# Modulo_Telemetros.net
KiCad netlist of a schematic drawn in Altium Designer
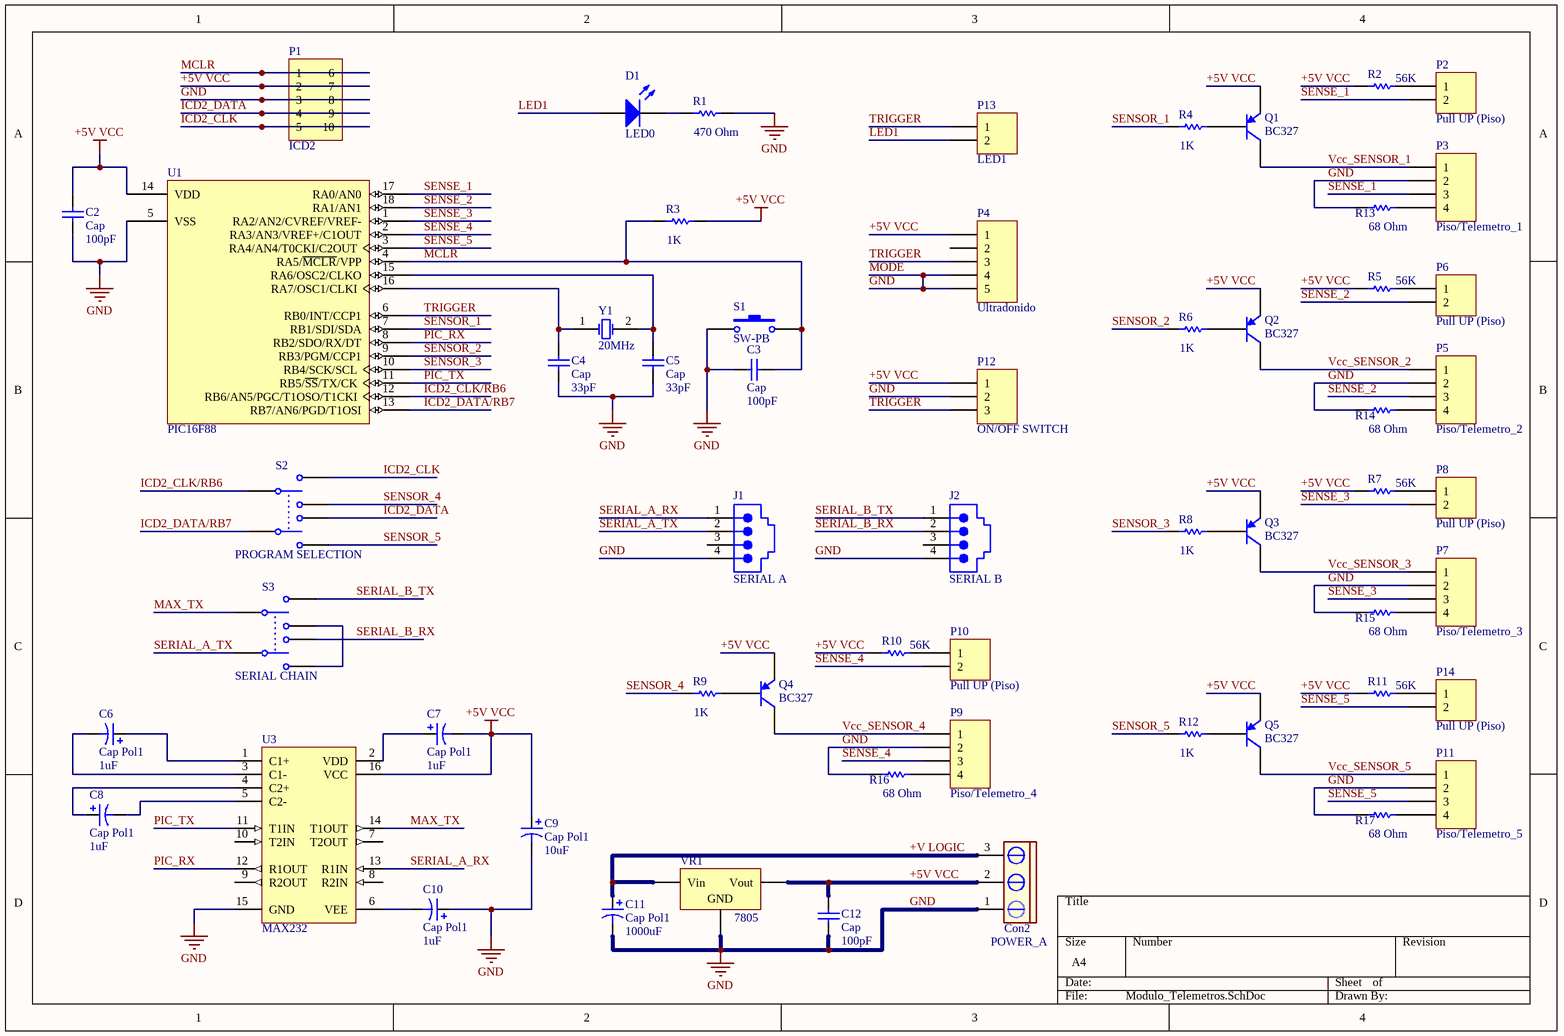
[diagram p0: Modulo_Telemetros.SchDoc]

(export (version "E")
  (design (tool "Eeschema 10.0.6"))
  (components
    (comp (ref "C2")
      (value "Cap")
      (footprint "CAPR2.54-5.1x3.2")
      (description "Capacitor")
      (fields (field (name "ALTIUM_VALUE") "100pF") (field (name "PUBLISHER") "Altium Limited"))
      (libsource (lib "Miscellaneous Devices") (part "Cap"))
    )
    (comp (ref "C3")
      (value "Cap")
      (footprint "CAPR2.54-5.1x3.2")
      (description "Capacitor")
      (fields (field (name "ALTIUM_VALUE") "100pF") (field (name "PUBLISHER") "Altium Limited"))
      (libsource (lib "Miscellaneous Devices") (part "Cap"))
    )
    (comp (ref "C4")
      (value "Cap")
      (footprint "CAPR2.54-5.1x3.2")
      (description "Capacitor")
      (fields (field (name "ALTIUM_VALUE") "33pF") (field (name "PUBLISHER") "Altium Limited"))
      (libsource (lib "Miscellaneous Devices") (part "Cap"))
    )
    (comp (ref "C5")
      (value "Cap")
      (footprint "CAPR2.54-5.1x3.2")
      (description "Capacitor")
      (fields (field (name "ALTIUM_VALUE") "33pF") (field (name "PUBLISHER") "Altium Limited"))
      (libsource (lib "Miscellaneous Devices") (part "Cap"))
    )
    (comp (ref "C6")
      (value "Cap Pol1")
      (footprint "CAPPR2-5x6.8")
      (description "Polarized Capacitor (Radial)")
      (fields (field (name "ALTIUM_VALUE") "1uF") (field (name "PUBLISHER") "Altium Limited"))
      (libsource (lib "Miscellaneous Devices") (part "Cap Pol1"))
    )
    (comp (ref "C7")
      (value "Cap Pol1")
      (footprint "CAPPR2-5x6.8")
      (description "Polarized Capacitor (Radial)")
      (fields (field (name "ALTIUM_VALUE") "1uF") (field (name "PUBLISHER") "Altium Limited"))
      (libsource (lib "Miscellaneous Devices") (part "Cap Pol1"))
    )
    (comp (ref "C8")
      (value "Cap Pol1")
      (footprint "CAPPR2-5x6.8")
      (description "Polarized Capacitor (Radial)")
      (fields (field (name "ALTIUM_VALUE") "1uF") (field (name "PUBLISHER") "Altium Limited"))
      (libsource (lib "Miscellaneous Devices") (part "Cap Pol1"))
    )
    (comp (ref "C9")
      (value "Cap Pol1")
      (footprint "CAPPR2-5x6.8")
      (description "Polarized Capacitor (Radial)")
      (fields (field (name "ALTIUM_VALUE") "10uF") (field (name "PUBLISHER") "Altium Limited"))
      (libsource (lib "Miscellaneous Devices") (part "Cap Pol1"))
    )
    (comp (ref "C10")
      (value "Cap Pol1")
      (footprint "CAPPR2-5x6.8")
      (description "Polarized Capacitor (Radial)")
      (fields (field (name "ALTIUM_VALUE") "1uF") (field (name "PUBLISHER") "Altium Limited"))
      (libsource (lib "Miscellaneous Devices") (part "Cap Pol1"))
    )
    (comp (ref "C11")
      (value "Cap Pol1")
      (footprint "RB5-10.5")
      (description "Polarized Capacitor (Radial)")
      (fields (field (name "ALTIUM_VALUE") "1000uF") (field (name "PUBLISHER") "Altium Limited"))
      (libsource (lib "Miscellaneous Devices") (part "Cap Pol1"))
    )
    (comp (ref "C12")
      (value "Cap")
      (footprint "CAPR2.54-5.1x3.2")
      (description "Capacitor")
      (fields (field (name "ALTIUM_VALUE") "100pF") (field (name "PUBLISHER") "Altium Limited"))
      (libsource (lib "Miscellaneous Devices") (part "Cap"))
    )
    (comp (ref "Con2")
      (value "POWER_A")
      (footprint "My_CN3")
      (description "Connector green screw")
      (libsource (lib "Protel_Library") (part "CON3 pin Green"))
    )
    (comp (ref "D1")
      (value "LED0")
      (footprint "LED-0")
      (description "Typical INFRARED GaAs LED")
      (fields (field (name "PUBLISHER") "Altium Limited"))
      (libsource (lib "Miscellaneous Devices") (part "LED0"))
    )
    (comp (ref "J1")
      (value "SERIAL A")
      (footprint "15-43-6245")
      (description "Right Angle, Standard Profile, RJ45-Keyed, Flange Mount PCB Jack")
      (fields (field (name "PUBLISHER") "Altium Limited"))
      (libsource (lib "Molex Modular Jack Right Angle") (part "15-43-6245"))
    )
    (comp (ref "J2")
      (value "SERIAL B")
      (footprint "15-43-6245")
      (description "Right Angle, Standard Profile, RJ45-Keyed, Flange Mount PCB Jack")
      (fields (field (name "PUBLISHER") "Altium Limited"))
      (libsource (lib "Molex Modular Jack Right Angle") (part "15-43-6245"))
    )
    (comp (ref "P1")
      (value "ICD2")
      (footprint "HEADER10_5x2_B")
      (description "Header, 5-Pin, Dual row")
      (fields (field (name "PUBLISHER") "Altium Limited"))
      (libsource (lib "Miscellaneous Connectors") (part "Header 5X2A"))
    )
    (comp (ref "P2")
      (value "Pull UP (Piso)")
      (footprint "HDR1X2")
      (description "Header, 2-Pin")
      (fields (field (name "PUBLISHER") "Altium Limited"))
      (libsource (lib "Miscellaneous Connectors") (part "Header 2"))
    )
    (comp (ref "P3")
      (value "Piso/Telemetro_1")
      (footprint "HDR1X4")
      (description "Header, 4-Pin")
      (fields (field (name "PUBLISHER") "Altium Limited"))
      (libsource (lib "Miscellaneous Connectors") (part "Header 4"))
    )
    (comp (ref "P4")
      (value "Ultradonido")
      (footprint "HDR1X5")
      (description "Header, 5-Pin")
      (fields (field (name "PUBLISHER") "Altium Limited"))
      (libsource (lib "Miscellaneous Connectors") (part "Header 5"))
    )
    (comp (ref "P5")
      (value "Piso/Telemetro_2")
      (footprint "HDR1X4")
      (description "Header, 4-Pin")
      (fields (field (name "PUBLISHER") "Altium Limited"))
      (libsource (lib "Miscellaneous Connectors") (part "Header 4"))
    )
    (comp (ref "P6")
      (value "Pull UP (Piso)")
      (footprint "HDR1X2")
      (description "Header, 2-Pin")
      (fields (field (name "PUBLISHER") "Altium Limited"))
      (libsource (lib "Miscellaneous Connectors") (part "Header 2"))
    )
    (comp (ref "P7")
      (value "Piso/Telemetro_3")
      (footprint "HDR1X4")
      (description "Header, 4-Pin")
      (fields (field (name "PUBLISHER") "Altium Limited"))
      (libsource (lib "Miscellaneous Connectors") (part "Header 4"))
    )
    (comp (ref "P8")
      (value "Pull UP (Piso)")
      (footprint "HDR1X2")
      (description "Header, 2-Pin")
      (fields (field (name "PUBLISHER") "Altium Limited"))
      (libsource (lib "Miscellaneous Connectors") (part "Header 2"))
    )
    (comp (ref "P9")
      (value "Piso/Telemetro_4")
      (footprint "HDR1X4")
      (description "Header, 4-Pin")
      (fields (field (name "PUBLISHER") "Altium Limited"))
      (libsource (lib "Miscellaneous Connectors") (part "Header 4"))
    )
    (comp (ref "P10")
      (value "Pull UP (Piso)")
      (footprint "HDR1X2")
      (description "Header, 2-Pin")
      (fields (field (name "PUBLISHER") "Altium Limited"))
      (libsource (lib "Miscellaneous Connectors") (part "Header 2"))
    )
    (comp (ref "P11")
      (value "Piso/Telemetro_5")
      (footprint "HDR1X4")
      (description "Header, 4-Pin")
      (fields (field (name "PUBLISHER") "Altium Limited"))
      (libsource (lib "Miscellaneous Connectors") (part "Header 4"))
    )
    (comp (ref "P12")
      (value "ON/OFF SWITCH")
      (footprint "HDR1X3")
      (description "Header, 3-Pin")
      (fields (field (name "PUBLISHER") "Altium Limited"))
      (libsource (lib "Miscellaneous Connectors") (part "Header 3"))
    )
    (comp (ref "P13")
      (value "LED1")
      (footprint "HDR1X2")
      (description "Header, 2-Pin")
      (fields (field (name "PUBLISHER") "Altium Limited"))
      (libsource (lib "Miscellaneous Connectors") (part "Header 2"))
    )
    (comp (ref "P14")
      (value "Pull UP (Piso)")
      (footprint "HDR1X2")
      (description "Header, 2-Pin")
      (fields (field (name "PUBLISHER") "Altium Limited"))
      (libsource (lib "Miscellaneous Connectors") (part "Header 2"))
    )
    (comp (ref "Q1")
      (value "BC327")
      (footprint "TO-92A")
      (description "PNP Switching Transistor")
      (fields (field (name "PUBLISHER") "Altium Limited"))
      (libsource (lib "FSC Discrete BJT") (part "2N5771"))
    )
    (comp (ref "Q2")
      (value "BC327")
      (footprint "TO-92A")
      (description "PNP Switching Transistor")
      (fields (field (name "PUBLISHER") "Altium Limited"))
      (libsource (lib "FSC Discrete BJT") (part "2N5771"))
    )
    (comp (ref "Q3")
      (value "BC327")
      (footprint "TO-92A")
      (description "PNP Switching Transistor")
      (fields (field (name "PUBLISHER") "Altium Limited"))
      (libsource (lib "FSC Discrete BJT") (part "2N5771"))
    )
    (comp (ref "Q4")
      (value "BC327")
      (footprint "TO-92A")
      (description "PNP Switching Transistor")
      (fields (field (name "PUBLISHER") "Altium Limited"))
      (libsource (lib "FSC Discrete BJT") (part "2N5771"))
    )
    (comp (ref "Q5")
      (value "BC327")
      (footprint "TO-92A")
      (description "PNP Switching Transistor")
      (fields (field (name "PUBLISHER") "Altium Limited"))
      (libsource (lib "FSC Discrete BJT") (part "2N5771"))
    )
    (comp (ref "R1")
      (value "470 Ohm")
      (footprint "AXIAL-0.3")
      (description "Resistor")
      (fields (field (name "Comment") "Res1") (field (name "PUBLISHER") "Altium Limited"))
      (libsource (lib "Miscellaneous Devices") (part "Res1"))
    )
    (comp (ref "R2")
      (value "56K")
      (footprint "AXIAL-0.3")
      (description "Resistor")
      (fields (field (name "Comment") "Res1") (field (name "PUBLISHER") "Altium Limited"))
      (libsource (lib "Miscellaneous Devices") (part "Res1"))
    )
    (comp (ref "R3")
      (value "1K")
      (footprint "AXIAL-0.3")
      (description "Resistor")
      (fields (field (name "Comment") "Res1") (field (name "PUBLISHER") "Altium Limited"))
      (libsource (lib "Miscellaneous Devices") (part "Res1"))
    )
    (comp (ref "R4")
      (value "1K")
      (footprint "AXIAL-0.3")
      (description "Resistor")
      (fields (field (name "Comment") "Res1") (field (name "PUBLISHER") "Altium Limited"))
      (libsource (lib "Miscellaneous Devices") (part "Res1"))
    )
    (comp (ref "R5")
      (value "56K")
      (footprint "AXIAL-0.3")
      (description "Resistor")
      (fields (field (name "Comment") "Res1") (field (name "PUBLISHER") "Altium Limited"))
      (libsource (lib "Miscellaneous Devices") (part "Res1"))
    )
    (comp (ref "R6")
      (value "1K")
      (footprint "AXIAL-0.3")
      (description "Resistor")
      (fields (field (name "Comment") "Res1") (field (name "PUBLISHER") "Altium Limited"))
      (libsource (lib "Miscellaneous Devices") (part "Res1"))
    )
    (comp (ref "R7")
      (value "56K")
      (footprint "AXIAL-0.3")
      (description "Resistor")
      (fields (field (name "Comment") "Res1") (field (name "PUBLISHER") "Altium Limited"))
      (libsource (lib "Miscellaneous Devices") (part "Res1"))
    )
    (comp (ref "R8")
      (value "1K")
      (footprint "AXIAL-0.3")
      (description "Resistor")
      (fields (field (name "Comment") "Res1") (field (name "PUBLISHER") "Altium Limited"))
      (libsource (lib "Miscellaneous Devices") (part "Res1"))
    )
    (comp (ref "R9")
      (value "1K")
      (footprint "AXIAL-0.3")
      (description "Resistor")
      (fields (field (name "Comment") "Res1") (field (name "PUBLISHER") "Altium Limited"))
      (libsource (lib "Miscellaneous Devices") (part "Res1"))
    )
    (comp (ref "R10")
      (value "56K")
      (footprint "AXIAL-0.3")
      (description "Resistor")
      (fields (field (name "Comment") "Res1") (field (name "PUBLISHER") "Altium Limited"))
      (libsource (lib "Miscellaneous Devices") (part "Res1"))
    )
    (comp (ref "R11")
      (value "56K")
      (footprint "AXIAL-0.3")
      (description "Resistor")
      (fields (field (name "Comment") "Res1") (field (name "PUBLISHER") "Altium Limited"))
      (libsource (lib "Miscellaneous Devices") (part "Res1"))
    )
    (comp (ref "R12")
      (value "1K")
      (footprint "AXIAL-0.3")
      (description "Resistor")
      (fields (field (name "Comment") "Res1") (field (name "PUBLISHER") "Altium Limited"))
      (libsource (lib "Miscellaneous Devices") (part "Res1"))
    )
    (comp (ref "R13")
      (value "68 Ohm")
      (footprint "AXIAL-0.3")
      (description "Resistor")
      (fields (field (name "Comment") "Res1") (field (name "PUBLISHER") "Altium Limited"))
      (libsource (lib "Miscellaneous Devices") (part "Res1"))
    )
    (comp (ref "R14")
      (value "68 Ohm")
      (footprint "AXIAL-0.3")
      (description "Resistor")
      (fields (field (name "Comment") "Res1") (field (name "PUBLISHER") "Altium Limited"))
      (libsource (lib "Miscellaneous Devices") (part "Res1"))
    )
    (comp (ref "R15")
      (value "68 Ohm")
      (footprint "AXIAL-0.3")
      (description "Resistor")
      (fields (field (name "Comment") "Res1") (field (name "PUBLISHER") "Altium Limited"))
      (libsource (lib "Miscellaneous Devices") (part "Res1"))
    )
    (comp (ref "R16")
      (value "68 Ohm")
      (footprint "AXIAL-0.3")
      (description "Resistor")
      (fields (field (name "Comment") "Res1") (field (name "PUBLISHER") "Altium Limited"))
      (libsource (lib "Miscellaneous Devices") (part "Res1"))
    )
    (comp (ref "R17")
      (value "68 Ohm")
      (footprint "AXIAL-0.3")
      (description "Resistor")
      (fields (field (name "Comment") "Res1") (field (name "PUBLISHER") "Altium Limited"))
      (libsource (lib "Miscellaneous Devices") (part "Res1"))
    )
    (comp (ref "S1")
      (value "SW-PB")
      (footprint "TS-063")
      (description "Switch")
      (fields (field (name "PUBLISHER") "Altium Limited"))
      (libsource (lib "Miscellaneous Devices") (part "SW-PB"))
    )
    (comp (ref "S2")
      (value "PROGRAM SELECTION")
      (footprint "LD-202mini")
      (description "Double-Pole, Double-Throw Switch")
      (fields (field (name "PUBLISHER") "Altium Limited"))
      (libsource (lib "Miscellaneous Devices") (part "SW-DPDT"))
    )
    (comp (ref "S3")
      (value "SERIAL CHAIN")
      (footprint "LD-202mini")
      (description "Double-Pole, Double-Throw Switch")
      (fields (field (name "PUBLISHER") "Altium Limited"))
      (libsource (lib "Miscellaneous Devices") (part "SW-DPDT"))
    )
    (comp (ref "U1")
      (value "PIC16F88")
      (footprint "PDIP300-P18")
      (fields (field (name "PUBLISHER") "Altium Limited"))
      (libsource (lib "Microchip Microcontroller 8-Bit PIC16") (part "PIC16F88-E/P"))
    )
    (comp (ref "U3")
      (value "MAX232")
      (footprint "PE16A")
      (description "+5V Powered, Multi-Channel RS-232 Driver/Receiver")
      (fields (field (name "PUBLISHER") "Altium Limited"))
      (libsource (lib "Maxim Communication Transceiver") (part "MAX232ACPE"))
    )
    (comp (ref "VR1")
      (value "7805")
      (footprint "My_TO-220")
      (description "Voltage Regulator")
      (fields (field (name "PUBLISHER") "Altium Limited"))
      (libsource (lib "Miscellaneous Devices") (part "Volt Reg"))
    )
    (comp (ref "Y1")
      (value "20MHz")
      (footprint "My_Crystal")
      (description "Crystal Oscillator")
      (fields (field (name "PUBLISHER") "Altium Limited"))
      (libsource (lib "Miscellaneous Devices") (part "XTAL"))
    )
  )
  (nets
    (net (code "1") (name "+5V VCC") (class "Default")
      (node (ref "C12") (pin "2") (pinfunction "2_2") (pintype "passive"))
      (node (ref "C2") (pin "2") (pinfunction "2_2") (pintype "passive"))
      (node (ref "C7") (pin "2") (pinfunction "2_2") (pintype "passive"))
      (node (ref "C9") (pin "1") (pinfunction "1_1") (pintype "passive"))
      (node (ref "Con2") (pin "2") (pinfunction "2_2") (pintype "passive"))
      (node (ref "P1") (pin "2") (pinfunction "2_2") (pintype "passive"))
      (node (ref "P1") (pin "7") (pinfunction "7_7") (pintype "passive"))
      (node (ref "P12") (pin "1") (pinfunction "1_1") (pintype "passive"))
      (node (ref "P4") (pin "1") (pinfunction "1_1") (pintype "passive"))
      (node (ref "Q1") (pin "1") (pinfunction "E_1") (pintype "passive"))
      (node (ref "Q2") (pin "1") (pinfunction "E_1") (pintype "passive"))
      (node (ref "Q3") (pin "1") (pinfunction "E_1") (pintype "passive"))
      (node (ref "Q4") (pin "1") (pinfunction "E_1") (pintype "passive"))
      (node (ref "Q5") (pin "1") (pinfunction "E_1") (pintype "passive"))
      (node (ref "R10") (pin "1") (pinfunction "1_1") (pintype "passive"))
      (node (ref "R11") (pin "1") (pinfunction "1_1") (pintype "passive"))
      (node (ref "R2") (pin "1") (pinfunction "1_1") (pintype "passive"))
      (node (ref "R3") (pin "2") (pinfunction "2_2") (pintype "passive"))
      (node (ref "R5") (pin "1") (pinfunction "1_1") (pintype "passive"))
      (node (ref "R7") (pin "1") (pinfunction "1_1") (pintype "passive"))
      (node (ref "U1") (pin "14") (pinfunction "VDD_14") (pintype "power_in"))
      (node (ref "U3") (pin "16") (pinfunction "VCC_16") (pintype "power_in"))
      (node (ref "VR1") (pin "3") (pinfunction "Vout_3") (pintype "passive"))
    )
    (net (code "2") (name "/+V LOGIC") (class "Default")
      (node (ref "C11") (pin "1") (pinfunction "1_1") (pintype "passive"))
      (node (ref "Con2") (pin "3") (pinfunction "3_3") (pintype "passive"))
      (node (ref "VR1") (pin "1") (pinfunction "Vin_1") (pintype "passive"))
    )
    (net (code "3") (name "/ICD2_CLK") (class "Default")
      (node (ref "P1") (pin "10") (pinfunction "10_10") (pintype "passive"))
      (node (ref "P1") (pin "5") (pinfunction "5_5") (pintype "passive"))
      (node (ref "S2") (pin "2") (pinfunction "2_2") (pintype "passive"))
    )
    (net (code "4") (name "/ICD2_CLK{slash}RB6") (class "Default")
      (node (ref "S2") (pin "1") (pinfunction "1_1") (pintype "passive"))
      (node (ref "U1") (pin "12") (pinfunction "RB6/AN5/PGC/T1OSO/T1CKI_12") (pintype "bidirectional"))
    )
    (net (code "5") (name "/ICD2_DATA") (class "Default")
      (node (ref "P1") (pin "4") (pinfunction "4_4") (pintype "passive"))
      (node (ref "P1") (pin "9") (pinfunction "9_9") (pintype "passive"))
      (node (ref "S2") (pin "5") (pinfunction "5_5") (pintype "passive"))
    )
    (net (code "6") (name "/ICD2_DATA{slash}RB7") (class "Default")
      (node (ref "S2") (pin "4") (pinfunction "4_4") (pintype "passive"))
      (node (ref "U1") (pin "13") (pinfunction "RB7/AN6/PGD/T1OSI_13") (pintype "bidirectional"))
    )
    (net (code "7") (name "/LED1") (class "Default")
      (node (ref "D1") (pin "1") (pinfunction "A_1") (pintype "passive"))
      (node (ref "P13") (pin "2") (pinfunction "2_2") (pintype "passive"))
    )
    (net (code "8") (name "/MAX_TX") (class "Default")
      (node (ref "S3") (pin "1") (pinfunction "1_1") (pintype "passive"))
      (node (ref "U3") (pin "14") (pinfunction "T1OUT_14") (pintype "output"))
    )
    (net (code "9") (name "/MCLR") (class "Default")
      (node (ref "C3") (pin "2") (pinfunction "2_2") (pintype "passive"))
      (node (ref "P1") (pin "1") (pinfunction "1_1") (pintype "passive"))
      (node (ref "P1") (pin "6") (pinfunction "6_6") (pintype "passive"))
      (node (ref "R3") (pin "1") (pinfunction "1_1") (pintype "passive"))
      (node (ref "S1") (pin "2") (pinfunction "2_2") (pintype "passive"))
      (node (ref "U1") (pin "4") (pinfunction "RA5/~{MCLR}/VPP_4") (pintype "bidirectional"))
    )
    (net (code "10") (name "/PIC_RX") (class "Default")
      (node (ref "U1") (pin "8") (pinfunction "RB2/SDO/RX/DT_8") (pintype "bidirectional"))
      (node (ref "U3") (pin "12") (pinfunction "R1OUT_12") (pintype "output"))
    )
    (net (code "11") (name "/PIC_TX") (class "Default")
      (node (ref "U1") (pin "11") (pinfunction "RB5/~{SS}/TX/CK_11") (pintype "bidirectional"))
      (node (ref "U3") (pin "11") (pinfunction "T1IN_11") (pintype "input"))
    )
    (net (code "12") (name "/SENSE_1") (class "Default")
      (node (ref "P2") (pin "2") (pinfunction "2_2") (pintype "passive"))
      (node (ref "P3") (pin "3") (pinfunction "3_3") (pintype "passive"))
      (node (ref "U1") (pin "17") (pinfunction "RA0/AN0_17") (pintype "bidirectional"))
    )
    (net (code "13") (name "/SENSE_2") (class "Default")
      (node (ref "P5") (pin "3") (pinfunction "3_3") (pintype "passive"))
      (node (ref "P6") (pin "2") (pinfunction "2_2") (pintype "passive"))
      (node (ref "U1") (pin "18") (pinfunction "RA1/AN1_18") (pintype "bidirectional"))
    )
    (net (code "14") (name "/SENSE_3") (class "Default")
      (node (ref "P7") (pin "3") (pinfunction "3_3") (pintype "passive"))
      (node (ref "P8") (pin "2") (pinfunction "2_2") (pintype "passive"))
      (node (ref "U1") (pin "1") (pinfunction "RA2/AN2/CVREF/VREF-_1") (pintype "bidirectional"))
    )
    (net (code "15") (name "/SENSE_4") (class "Default")
      (node (ref "P10") (pin "2") (pinfunction "2_2") (pintype "passive"))
      (node (ref "P9") (pin "3") (pinfunction "3_3") (pintype "passive"))
      (node (ref "U1") (pin "2") (pinfunction "RA3/AN3/VREF+/C1OUT_2") (pintype "bidirectional"))
    )
    (net (code "16") (name "/SENSE_5") (class "Default")
      (node (ref "P11") (pin "3") (pinfunction "3_3") (pintype "passive"))
      (node (ref "P14") (pin "2") (pinfunction "2_2") (pintype "passive"))
      (node (ref "U1") (pin "3") (pinfunction "RA4/AN4/T0CKI/C2OUT_3") (pintype "bidirectional"))
    )
    (net (code "17") (name "/SENSOR_1") (class "Default")
      (node (ref "R4") (pin "1") (pinfunction "1_1") (pintype "passive"))
      (node (ref "U1") (pin "7") (pinfunction "RB1/SDI/SDA_7") (pintype "bidirectional"))
    )
    (net (code "18") (name "/SENSOR_2") (class "Default")
      (node (ref "R6") (pin "1") (pinfunction "1_1") (pintype "passive"))
      (node (ref "U1") (pin "9") (pinfunction "RB3/PGM/CCP1_9") (pintype "bidirectional"))
    )
    (net (code "19") (name "/SENSOR_3") (class "Default")
      (node (ref "R8") (pin "1") (pinfunction "1_1") (pintype "passive"))
      (node (ref "U1") (pin "10") (pinfunction "RB4/SCK/SCL_10") (pintype "bidirectional"))
    )
    (net (code "20") (name "/SENSOR_4") (class "Default")
      (node (ref "R9") (pin "1") (pinfunction "1_1") (pintype "passive"))
      (node (ref "S2") (pin "3") (pinfunction "3_3") (pintype "passive"))
    )
    (net (code "21") (name "/SENSOR_5") (class "Default")
      (node (ref "R12") (pin "1") (pinfunction "1_1") (pintype "passive"))
      (node (ref "S2") (pin "6") (pinfunction "6_6") (pintype "passive"))
    )
    (net (code "22") (name "/SERIAL_A_RX") (class "Default")
      (node (ref "J1") (pin "1") (pinfunction "1_1") (pintype "passive"))
      (node (ref "U3") (pin "13") (pinfunction "R1IN_13") (pintype "input"))
    )
    (net (code "23") (name "/SERIAL_A_TX") (class "Default")
      (node (ref "J1") (pin "2") (pinfunction "2_2") (pintype "passive"))
      (node (ref "S3") (pin "4") (pinfunction "4_4") (pintype "passive"))
    )
    (net (code "24") (name "/SERIAL_B_RX") (class "Default")
      (node (ref "J2") (pin "2") (pinfunction "2_2") (pintype "passive"))
      (node (ref "S3") (pin "5") (pinfunction "5_5") (pintype "passive"))
    )
    (net (code "25") (name "/SERIAL_B_TX") (class "Default")
      (node (ref "J2") (pin "1") (pinfunction "1_1") (pintype "passive"))
      (node (ref "S3") (pin "2") (pinfunction "2_2") (pintype "passive"))
    )
    (net (code "26") (name "/TRIGGER") (class "Default")
      (node (ref "P12") (pin "3") (pinfunction "3_3") (pintype "passive"))
      (node (ref "P13") (pin "1") (pinfunction "1_1") (pintype "passive"))
      (node (ref "P4") (pin "3") (pinfunction "3_3") (pintype "passive"))
      (node (ref "U1") (pin "6") (pinfunction "RB0/INT/CCP1_6") (pintype "bidirectional"))
    )
    (net (code "27") (name "/Vcc_SENSOR_1") (class "Default")
      (node (ref "P3") (pin "1") (pinfunction "1_1") (pintype "passive"))
      (node (ref "Q1") (pin "3") (pinfunction "C_3") (pintype "passive"))
    )
    (net (code "28") (name "/Vcc_SENSOR_2") (class "Default")
      (node (ref "P5") (pin "1") (pinfunction "1_1") (pintype "passive"))
      (node (ref "Q2") (pin "3") (pinfunction "C_3") (pintype "passive"))
    )
    (net (code "29") (name "/Vcc_SENSOR_3") (class "Default")
      (node (ref "P7") (pin "1") (pinfunction "1_1") (pintype "passive"))
      (node (ref "Q3") (pin "3") (pinfunction "C_3") (pintype "passive"))
    )
    (net (code "30") (name "/Vcc_SENSOR_4") (class "Default")
      (node (ref "P9") (pin "1") (pinfunction "1_1") (pintype "passive"))
      (node (ref "Q4") (pin "3") (pinfunction "C_3") (pintype "passive"))
    )
    (net (code "31") (name "/Vcc_SENSOR_5") (class "Default")
      (node (ref "P11") (pin "1") (pinfunction "1_1") (pintype "passive"))
      (node (ref "Q5") (pin "3") (pinfunction "C_3") (pintype "passive"))
    )
    (net (code "32") (name "GND") (class "Default")
      (node (ref "C10") (pin "1") (pinfunction "1_1") (pintype "passive"))
      (node (ref "C11") (pin "2") (pinfunction "2_2") (pintype "passive"))
      (node (ref "C12") (pin "1") (pinfunction "1_1") (pintype "passive"))
      (node (ref "C2") (pin "1") (pinfunction "1_1") (pintype "passive"))
      (node (ref "C3") (pin "1") (pinfunction "1_1") (pintype "passive"))
      (node (ref "C4") (pin "1") (pinfunction "1_1") (pintype "passive"))
      (node (ref "C5") (pin "1") (pinfunction "1_1") (pintype "passive"))
      (node (ref "C9") (pin "2") (pinfunction "2_2") (pintype "passive"))
      (node (ref "Con2") (pin "1") (pinfunction "1_1") (pintype "passive"))
      (node (ref "J1") (pin "4") (pinfunction "4_4") (pintype "passive"))
      (node (ref "J2") (pin "4") (pinfunction "4_4") (pintype "passive"))
      (node (ref "P1") (pin "3") (pinfunction "3_3") (pintype "passive"))
      (node (ref "P1") (pin "8") (pinfunction "8_8") (pintype "passive"))
      (node (ref "P11") (pin "2") (pinfunction "2_2") (pintype "passive"))
      (node (ref "P12") (pin "2") (pinfunction "2_2") (pintype "passive"))
      (node (ref "P3") (pin "2") (pinfunction "2_2") (pintype "passive"))
      (node (ref "P4") (pin "4") (pinfunction "4_4") (pintype "passive"))
      (node (ref "P4") (pin "5") (pinfunction "5_5") (pintype "passive"))
      (node (ref "P5") (pin "2") (pinfunction "2_2") (pintype "passive"))
      (node (ref "P7") (pin "2") (pinfunction "2_2") (pintype "passive"))
      (node (ref "P9") (pin "2") (pinfunction "2_2") (pintype "passive"))
      (node (ref "R1") (pin "2") (pinfunction "2_2") (pintype "passive"))
      (node (ref "R13") (pin "1") (pinfunction "1_1") (pintype "passive"))
      (node (ref "R14") (pin "1") (pinfunction "1_1") (pintype "passive"))
      (node (ref "R15") (pin "1") (pinfunction "1_1") (pintype "passive"))
      (node (ref "R16") (pin "1") (pinfunction "1_1") (pintype "passive"))
      (node (ref "R17") (pin "1") (pinfunction "1_1") (pintype "passive"))
      (node (ref "S1") (pin "1") (pinfunction "1_1") (pintype "passive"))
      (node (ref "U1") (pin "5") (pinfunction "VSS_5") (pintype "power_in"))
      (node (ref "U3") (pin "15") (pinfunction "GND_15") (pintype "power_in"))
      (node (ref "VR1") (pin "2") (pinfunction "GND_2") (pintype "passive"))
    )
    (net (code "33") (name "Net-(D1-K)") (class "Default")
      (node (ref "D1") (pin "2") (pinfunction "K_2") (pintype "passive"))
      (node (ref "R1") (pin "1") (pinfunction "1_1") (pintype "passive"))
    )
    (net (code "34") (name "Net-(P2-Pad1)") (class "Default")
      (node (ref "P2") (pin "1") (pinfunction "1_1") (pintype "passive"))
      (node (ref "R2") (pin "2") (pinfunction "2_2") (pintype "passive"))
    )
    (net (code "35") (name "Net-(P3-Pad4)") (class "Default")
      (node (ref "P3") (pin "4") (pinfunction "4_4") (pintype "passive"))
      (node (ref "R13") (pin "2") (pinfunction "2_2") (pintype "passive"))
    )
    (net (code "36") (name "Net-(P5-Pad4)") (class "Default")
      (node (ref "P5") (pin "4") (pinfunction "4_4") (pintype "passive"))
      (node (ref "R14") (pin "2") (pinfunction "2_2") (pintype "passive"))
    )
    (net (code "37") (name "Net-(P6-Pad1)") (class "Default")
      (node (ref "P6") (pin "1") (pinfunction "1_1") (pintype "passive"))
      (node (ref "R5") (pin "2") (pinfunction "2_2") (pintype "passive"))
    )
    (net (code "38") (name "Net-(P7-Pad4)") (class "Default")
      (node (ref "P7") (pin "4") (pinfunction "4_4") (pintype "passive"))
      (node (ref "R15") (pin "2") (pinfunction "2_2") (pintype "passive"))
    )
    (net (code "39") (name "Net-(P8-Pad1)") (class "Default")
      (node (ref "P8") (pin "1") (pinfunction "1_1") (pintype "passive"))
      (node (ref "R7") (pin "2") (pinfunction "2_2") (pintype "passive"))
    )
    (net (code "40") (name "Net-(P9-Pad4)") (class "Default")
      (node (ref "P9") (pin "4") (pinfunction "4_4") (pintype "passive"))
      (node (ref "R16") (pin "2") (pinfunction "2_2") (pintype "passive"))
    )
    (net (code "41") (name "Net-(P10-Pad1)") (class "Default")
      (node (ref "P10") (pin "1") (pinfunction "1_1") (pintype "passive"))
      (node (ref "R10") (pin "2") (pinfunction "2_2") (pintype "passive"))
    )
    (net (code "42") (name "Net-(P11-Pad4)") (class "Default")
      (node (ref "P11") (pin "4") (pinfunction "4_4") (pintype "passive"))
      (node (ref "R17") (pin "2") (pinfunction "2_2") (pintype "passive"))
    )
    (net (code "43") (name "Net-(P14-Pad1)") (class "Default")
      (node (ref "P14") (pin "1") (pinfunction "1_1") (pintype "passive"))
      (node (ref "R11") (pin "2") (pinfunction "2_2") (pintype "passive"))
    )
    (net (code "44") (name "Net-(Q1-B)") (class "Default")
      (node (ref "Q1") (pin "2") (pinfunction "B_2") (pintype "passive"))
      (node (ref "R4") (pin "2") (pinfunction "2_2") (pintype "passive"))
    )
    (net (code "45") (name "Net-(Q2-B)") (class "Default")
      (node (ref "Q2") (pin "2") (pinfunction "B_2") (pintype "passive"))
      (node (ref "R6") (pin "2") (pinfunction "2_2") (pintype "passive"))
    )
    (net (code "46") (name "Net-(Q3-B)") (class "Default")
      (node (ref "Q3") (pin "2") (pinfunction "B_2") (pintype "passive"))
      (node (ref "R8") (pin "2") (pinfunction "2_2") (pintype "passive"))
    )
    (net (code "47") (name "Net-(Q4-B)") (class "Default")
      (node (ref "Q4") (pin "2") (pinfunction "B_2") (pintype "passive"))
      (node (ref "R9") (pin "2") (pinfunction "2_2") (pintype "passive"))
    )
    (net (code "48") (name "Net-(Q5-B)") (class "Default")
      (node (ref "Q5") (pin "2") (pinfunction "B_2") (pintype "passive"))
      (node (ref "R12") (pin "2") (pinfunction "2_2") (pintype "passive"))
    )
    (net (code "49") (name "Net-(S3-Pad3)") (class "Default")
      (node (ref "S3") (pin "3") (pinfunction "3_3") (pintype "passive"))
      (node (ref "S3") (pin "6") (pinfunction "6_6") (pintype "passive"))
    )
    (net (code "50") (name "Net-(U1-RA6{slash}OSC2{slash}CLKO)") (class "Default")
      (node (ref "C5") (pin "2") (pinfunction "2_2") (pintype "passive"))
      (node (ref "U1") (pin "15") (pinfunction "RA6/OSC2/CLKO_15") (pintype "bidirectional"))
      (node (ref "Y1") (pin "2") (pinfunction "OSC2_2") (pintype "passive"))
    )
    (net (code "51") (name "Net-(U1-RA7{slash}OSC1{slash}CLKI)") (class "Default")
      (node (ref "C4") (pin "2") (pinfunction "2_2") (pintype "passive"))
      (node (ref "U1") (pin "16") (pinfunction "RA7/OSC1/CLKI_16") (pintype "bidirectional"))
      (node (ref "Y1") (pin "1") (pinfunction "OSC1_1") (pintype "passive"))
    )
    (net (code "52") (name "Net-(U3-C1+)") (class "Default")
      (node (ref "C6") (pin "1") (pinfunction "1_1") (pintype "passive"))
      (node (ref "U3") (pin "1") (pinfunction "C1+_1") (pintype "passive"))
    )
    (net (code "53") (name "Net-(U3-C1-)") (class "Default")
      (node (ref "C6") (pin "2") (pinfunction "2_2") (pintype "passive"))
      (node (ref "U3") (pin "3") (pinfunction "C1-_3") (pintype "passive"))
    )
    (net (code "54") (name "Net-(U3-C2+)") (class "Default")
      (node (ref "C8") (pin "1") (pinfunction "1_1") (pintype "passive"))
      (node (ref "U3") (pin "4") (pinfunction "C2+_4") (pintype "passive"))
    )
    (net (code "55") (name "Net-(U3-C2-)") (class "Default")
      (node (ref "C8") (pin "2") (pinfunction "2_2") (pintype "passive"))
      (node (ref "U3") (pin "5") (pinfunction "C2-_5") (pintype "passive"))
    )
    (net (code "56") (name "Net-(U3-VDD)") (class "Default")
      (node (ref "C7") (pin "1") (pinfunction "1_1") (pintype "passive"))
      (node (ref "U3") (pin "2") (pinfunction "VDD_2") (pintype "power_in"))
    )
    (net (code "57") (name "Net-(U3-VEE)") (class "Default")
      (node (ref "C10") (pin "2") (pinfunction "2_2") (pintype "passive"))
      (node (ref "U3") (pin "6") (pinfunction "VEE_6") (pintype "power_in"))
    )
    (net (code "58") (name "unconnected-(J1-Pad3)") (class "Default")
      (node (ref "J1") (pin "3") (pinfunction "3_3") (pintype "passive"))
    )
    (net (code "59") (name "unconnected-(J2-Pad3)") (class "Default")
      (node (ref "J2") (pin "3") (pinfunction "3_3") (pintype "passive"))
    )
    (net (code "60") (name "unconnected-(P4-Pad2)") (class "Default")
      (node (ref "P4") (pin "2") (pinfunction "2_2") (pintype "passive"))
    )
    (net (code "61") (name "unconnected-(U3-R2IN-Pad8)") (class "Default")
      (node (ref "U3") (pin "8") (pinfunction "R2IN_8") (pintype "input"))
    )
    (net (code "62") (name "unconnected-(U3-R2OUT-Pad9)") (class "Default")
      (node (ref "U3") (pin "9") (pinfunction "R2OUT_9") (pintype "output"))
    )
    (net (code "63") (name "unconnected-(U3-T2IN-Pad10)") (class "Default")
      (node (ref "U3") (pin "10") (pinfunction "T2IN_10") (pintype "input"))
    )
    (net (code "64") (name "unconnected-(U3-T2OUT-Pad7)") (class "Default")
      (node (ref "U3") (pin "7") (pinfunction "T2OUT_7") (pintype "output"))
    )
  )
)
